# LED_Driver_-_2.net
KiCad netlist of a schematic drawn in Altium Designer
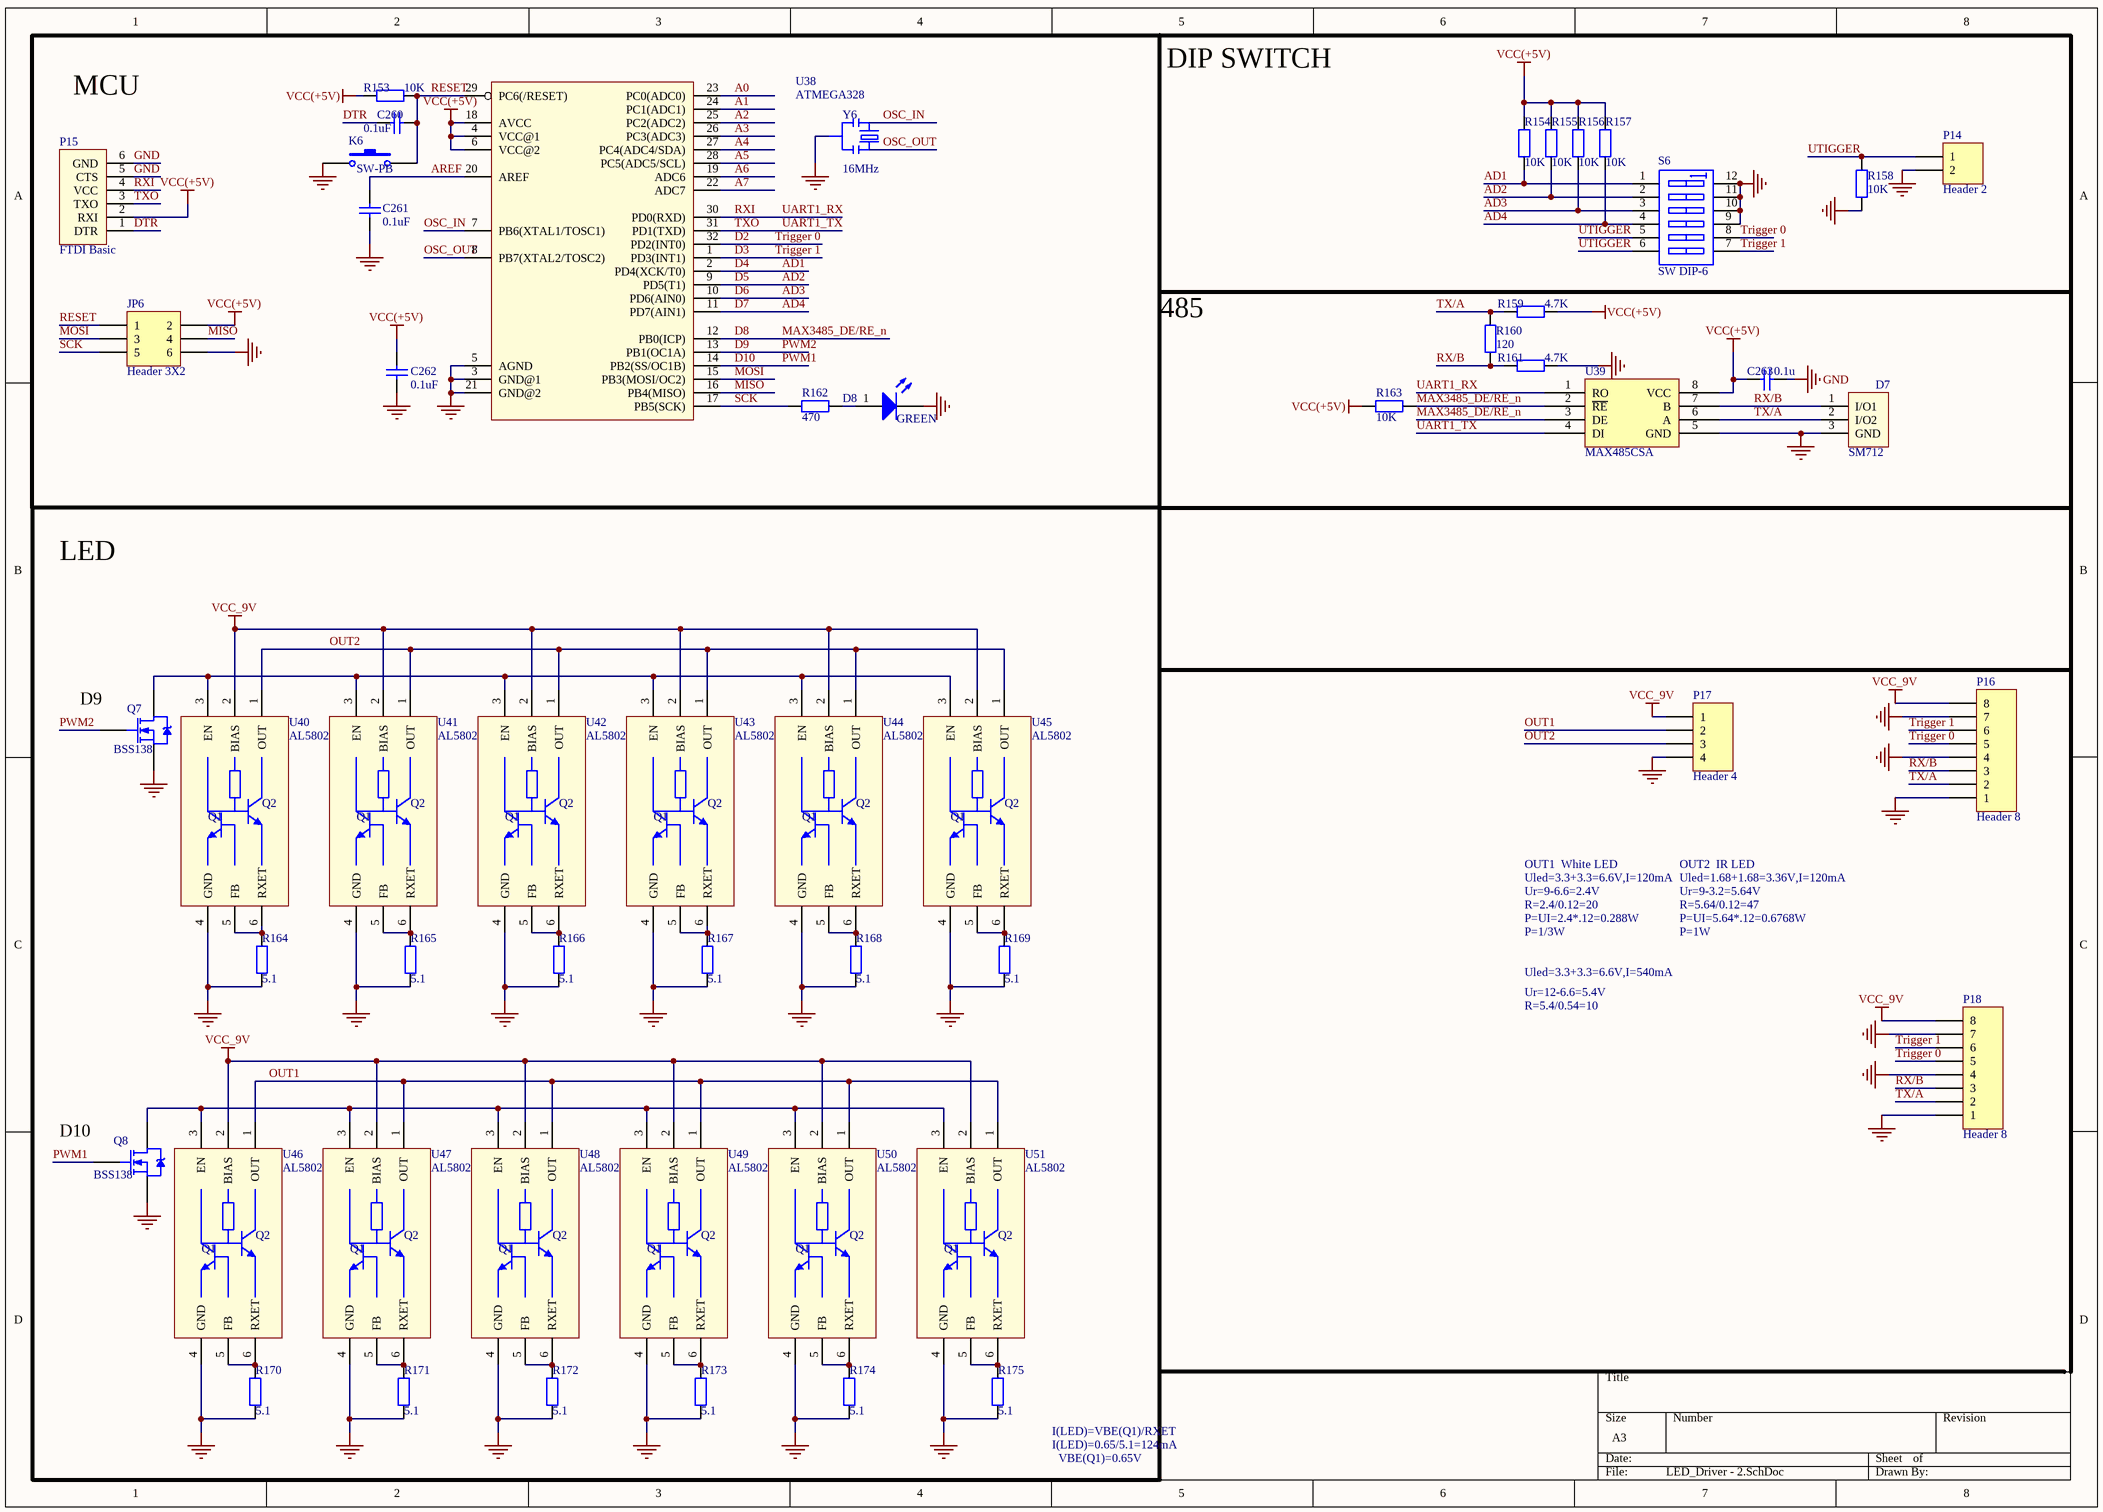
[diagram p0: LED_Driver - 2.SchDoc]

(export (version "E")
  (design (tool "Eeschema 10.0.6"))
  (components
    (comp (ref "C260")
      (value "0.1uF")
      (footprint "C0603")
      (description "Capacitor")
      (fields (field (name "IPARTNUMBER") "C100nF25V10%X7R") (field (name "VOLTAGE") "25V"))
      (libsource (lib "Schlib1") (part "CAP SMT C100nF25V10%X7R"))
    )
    (comp (ref "C261")
      (value "0.1uF")
      (footprint "C0603")
      (description "Capacitor")
      (fields (field (name "IPARTNUMBER") "C100nF25V10%X7R") (field (name "VOLTAGE") "25V"))
      (libsource (lib "Schlib1") (part "CAP SMT C100nF25V10%X7R"))
    )
    (comp (ref "C262")
      (value "0.1uF")
      (footprint "C0603")
      (description "Capacitor")
      (fields (field (name "IPARTNUMBER") "C100nF25V10%X7R") (field (name "VOLTAGE") "25V"))
      (libsource (lib "Schlib1") (part "CAP SMT C100nF25V10%X7R"))
    )
    (comp (ref "C263")
      (value "0.1u")
      (footprint "C0603")
      (description "Capacitor")
      (fields (field (name "PUBLISHER") "Altium Limited"))
      (libsource (lib "Miscellaneous Devices") (part "Cap"))
    )
    (comp (ref "D7")
      (value "SM712")
      (footprint "SOT23-3")
      (libsource (lib "STM32F4_CAM V2.0") (part "SM712"))
    )
    (comp (ref "D8")
      (value "GREEN")
      (footprint "LED0805")
      (description "Typical INFRARED GaAs LED")
      (fields (field (name "PUBLISHER") "Altium Limited"))
      (libsource (lib "DM642") (part "LED0"))
    )
    (comp (ref "JP6")
      (value "Header 3X2")
      (footprint "MHDR1X6")
      (description "Header, 3-Pin, Dual row")
      (fields (field (name "PUBLISHER") "Altium Limited"))
      (libsource (lib "Miscellaneous Connectors") (part "Header 3X2"))
    )
    (comp (ref "K6")
      (value "SW-PB")
      (footprint "157SW")
      (description "Switch")
      (fields (field (name "PUBLISHER") "Altium Limited"))
      (libsource (lib "Miscellaneous Devices") (part "SW-PB"))
    )
    (comp (ref "P14")
      (value "Header 2")
      (footprint "HDR1X2")
      (description "Header, 2-Pin")
      (fields (field (name "PUBLISHER") "Altium Limited"))
      (libsource (lib "Miscellaneous Connectors") (part "Header 2"))
    )
    (comp (ref "P15")
      (value "FTDI Basic")
      (footprint "MHDR1X6")
      (libsource (lib "PCB_Project1") (part "ARDUINO_SERIAL_PROGRAMPTH"))
    )
    (comp (ref "P16")
      (value "Header 8")
      (footprint "SH_1.25MM*8")
      (description "Header, 8-Pin")
      (fields (field (name "PUBLISHER") "Altium Limited"))
      (libsource (lib "Miscellaneous Connectors") (part "Header 8"))
    )
    (comp (ref "P17")
      (value "Header 4")
      (footprint "SMT_1.25MM*4")
      (description "Header, 4-Pin")
      (fields (field (name "PUBLISHER") "Altium Limited"))
      (libsource (lib "Miscellaneous Connectors") (part "Header 4"))
    )
    (comp (ref "P18")
      (value "Header 8")
      (footprint "SH_1.25MM*8")
      (description "Header, 8-Pin")
      (fields (field (name "PUBLISHER") "Altium Limited"))
      (libsource (lib "Miscellaneous Connectors") (part "Header 8"))
    )
    (comp (ref "Q7")
      (value "BSS138")
      (footprint "SOT-23 (Standard)")
      (fields
        (field (name "MANUFACTURER") "Fairchild Semiconductor")
        (field (name "MANUFACTURER PART NUMBER") "BSS123")
      )
      (libsource (lib "Miscellaneous_Devices") (part "NMOS"))
    )
    (comp (ref "Q8")
      (value "BSS138")
      (footprint "SOT-23 (Standard)")
      (fields
        (field (name "MANUFACTURER") "Fairchild Semiconductor")
        (field (name "MANUFACTURER PART NUMBER") "BSS123")
      )
      (libsource (lib "Miscellaneous_Devices") (part "NMOS"))
    )
    (comp (ref "R153")
      (value "10K")
      (footprint "R0603")
      (description "Resistor")
      (libsource (lib "") (part "Res2_2"))
    )
    (comp (ref "R154")
      (value "10K")
      (footprint "R0603")
      (description "Resistor")
      (libsource (lib "DM642") (part "Res2"))
    )
    (comp (ref "R155")
      (value "10K")
      (footprint "R0603")
      (description "Resistor")
      (libsource (lib "DM642") (part "Res2"))
    )
    (comp (ref "R156")
      (value "10K")
      (footprint "R0603")
      (description "Resistor")
      (libsource (lib "DM642") (part "Res2"))
    )
    (comp (ref "R157")
      (value "10K")
      (footprint "R0603")
      (description "Resistor")
      (libsource (lib "DM642") (part "Res2"))
    )
    (comp (ref "R158")
      (value "10K")
      (footprint "R0603")
      (description "Resistor")
      (fields (field (name "PUBLISHER") "Altium Limited"))
      (libsource (lib "Miscellaneous Devices") (part "Res2"))
    )
    (comp (ref "R159")
      (value "4.7K")
      (footprint "R0603")
      (description "Resistor")
      (libsource (lib "") (part "Res2_1"))
    )
    (comp (ref "R160")
      (value "120")
      (footprint "R0603")
      (description "Resistor")
      (libsource (lib "DM642") (part "Res2"))
    )
    (comp (ref "R161")
      (value "4.7K")
      (footprint "R0603")
      (description "Resistor")
      (libsource (lib "") (part "Res2_1"))
    )
    (comp (ref "R162")
      (value "470")
      (footprint "R0603")
      (description "Resistor")
      (libsource (lib "") (part "Res2_2"))
    )
    (comp (ref "R163")
      (value "10K")
      (footprint "R0603")
      (description "Resistor")
      (libsource (lib "") (part "Res2_1"))
    )
    (comp (ref "R164")
      (value "5.1")
      (footprint "R0603")
      (description "Resistor")
      (libsource (lib "DM642") (part "Res2"))
    )
    (comp (ref "R165")
      (value "5.1")
      (footprint "R0603")
      (description "Resistor")
      (libsource (lib "DM642") (part "Res2"))
    )
    (comp (ref "R166")
      (value "5.1")
      (footprint "R0603")
      (description "Resistor")
      (libsource (lib "DM642") (part "Res2"))
    )
    (comp (ref "R167")
      (value "5.1")
      (footprint "R0603")
      (description "Resistor")
      (libsource (lib "DM642") (part "Res2"))
    )
    (comp (ref "R168")
      (value "5.1")
      (footprint "R0603")
      (description "Resistor")
      (libsource (lib "DM642") (part "Res2"))
    )
    (comp (ref "R169")
      (value "5.1")
      (footprint "R0603")
      (description "Resistor")
      (libsource (lib "DM642") (part "Res2"))
    )
    (comp (ref "R170")
      (value "5.1")
      (footprint "R0603")
      (description "Resistor")
      (libsource (lib "DM642") (part "Res2"))
    )
    (comp (ref "R171")
      (value "5.1")
      (footprint "R0603")
      (description "Resistor")
      (libsource (lib "DM642") (part "Res2"))
    )
    (comp (ref "R172")
      (value "5.1")
      (footprint "R0603")
      (description "Resistor")
      (libsource (lib "DM642") (part "Res2"))
    )
    (comp (ref "R173")
      (value "5.1")
      (footprint "R0603")
      (description "Resistor")
      (libsource (lib "DM642") (part "Res2"))
    )
    (comp (ref "R174")
      (value "5.1")
      (footprint "R0603")
      (description "Resistor")
      (libsource (lib "DM642") (part "Res2"))
    )
    (comp (ref "R175")
      (value "5.1")
      (footprint "R0603")
      (description "Resistor")
      (libsource (lib "DM642") (part "Res2"))
    )
    (comp (ref "S6")
      (value "SW DIP-6")
      (footprint "DIP_SW_6WAY_SMD")
      (description "DIP Switch, 6 Position, SPST")
      (fields (field (name "PUBLISHER") "Altium Limited"))
      (libsource (lib "Miscellaneous Devices") (part "SW DIP-6"))
    )
    (comp (ref "U38")
      (value "ATMEGA328")
      (footprint "TQFP32-08")
      (libsource (lib "PCB_Project1") (part "ATMEGA168"))
    )
    (comp (ref "U39")
      (value "MAX485CSA")
      (footprint "SOIC-8")
      (libsource (lib "STM32F4_CAM V1.2") (part "MAX3485CSA"))
    )
    (comp (ref "U40") (value "AL5802") (footprint "SOT26") (libsource (lib "LED") (part "AL5802")))
    (comp (ref "U41") (value "AL5802") (footprint "SOT26") (libsource (lib "LED") (part "AL5802")))
    (comp (ref "U42") (value "AL5802") (footprint "SOT26") (libsource (lib "LED") (part "AL5802")))
    (comp (ref "U43") (value "AL5802") (footprint "SOT26") (libsource (lib "LED") (part "AL5802")))
    (comp (ref "U44") (value "AL5802") (footprint "SOT26") (libsource (lib "LED") (part "AL5802")))
    (comp (ref "U45") (value "AL5802") (footprint "SOT26") (libsource (lib "LED") (part "AL5802")))
    (comp (ref "U46") (value "AL5802") (footprint "SOT26") (libsource (lib "LED") (part "AL5802")))
    (comp (ref "U47") (value "AL5802") (footprint "SOT26") (libsource (lib "LED") (part "AL5802")))
    (comp (ref "U48") (value "AL5802") (footprint "SOT26") (libsource (lib "LED") (part "AL5802")))
    (comp (ref "U49") (value "AL5802") (footprint "SOT26") (libsource (lib "LED") (part "AL5802")))
    (comp (ref "U50") (value "AL5802") (footprint "SOT26") (libsource (lib "LED") (part "AL5802")))
    (comp (ref "U51") (value "AL5802") (footprint "SOT26") (libsource (lib "LED") (part "AL5802")))
    (comp (ref "Y6")
      (value "16MHz")
      (footprint "RESONATOR-SMD")
      (libsource (lib "SparkFun") (part "RESONATORSMD"))
    )
  )
  (nets
    (net (code "1") (name "/A0") (class "Default")
      (node (ref "U38") (pin "23") (pinfunction "PC0(ADC0)_23") (pintype "passive"))
    )
    (net (code "2") (name "/A1") (class "Default")
      (node (ref "U38") (pin "24") (pinfunction "PC1(ADC1)_24") (pintype "passive"))
    )
    (net (code "3") (name "/A2") (class "Default")
      (node (ref "U38") (pin "25") (pinfunction "PC2(ADC2)_25") (pintype "passive"))
    )
    (net (code "4") (name "/A3") (class "Default")
      (node (ref "U38") (pin "26") (pinfunction "PC3(ADC3)_26") (pintype "passive"))
    )
    (net (code "5") (name "/A4") (class "Default")
      (node (ref "U38") (pin "27") (pinfunction "PC4(ADC4/SDA)_27") (pintype "passive"))
    )
    (net (code "6") (name "/A5") (class "Default")
      (node (ref "U38") (pin "28") (pinfunction "PC5(ADC5/SCL)_28") (pintype "passive"))
    )
    (net (code "7") (name "/A6") (class "Default")
      (node (ref "U38") (pin "19") (pinfunction "ADC6_19") (pintype "passive"))
    )
    (net (code "8") (name "/A7") (class "Default")
      (node (ref "U38") (pin "22") (pinfunction "ADC7_22") (pintype "passive"))
    )
    (net (code "9") (name "/AD1") (class "Default")
      (node (ref "R154") (pin "2") (pinfunction "2_2") (pintype "passive"))
      (node (ref "S6") (pin "1") (pinfunction "A1_1") (pintype "passive"))
      (node (ref "U38") (pin "2") (pinfunction "PD4(XCK/T0)_2") (pintype "passive"))
    )
    (net (code "10") (name "/AD2") (class "Default")
      (node (ref "R155") (pin "2") (pinfunction "2_2") (pintype "passive"))
      (node (ref "S6") (pin "2") (pinfunction "A2_2") (pintype "passive"))
      (node (ref "U38") (pin "9") (pinfunction "PD5(T1)_9") (pintype "passive"))
    )
    (net (code "11") (name "/AD3") (class "Default")
      (node (ref "R156") (pin "2") (pinfunction "2_2") (pintype "passive"))
      (node (ref "S6") (pin "3") (pinfunction "A3_3") (pintype "passive"))
      (node (ref "U38") (pin "10") (pinfunction "PD6(AIN0)_10") (pintype "passive"))
    )
    (net (code "12") (name "/AD4") (class "Default")
      (node (ref "R157") (pin "2") (pinfunction "2_2") (pintype "passive"))
      (node (ref "S6") (pin "4") (pinfunction "A4_4") (pintype "passive"))
      (node (ref "U38") (pin "11") (pinfunction "PD7(AIN1)_11") (pintype "passive"))
    )
    (net (code "13") (name "/AREF") (class "Default")
      (node (ref "C261") (pin "2") (pinfunction "2_2") (pintype "passive"))
      (node (ref "U38") (pin "20") (pinfunction "AREF_20") (pintype "passive"))
    )
    (net (code "14") (name "/D2") (class "Default")
      (node (ref "P16") (pin "5") (pinfunction "5_5") (pintype "passive"))
      (node (ref "P18") (pin "5") (pinfunction "5_5") (pintype "passive"))
      (node (ref "S6") (pin "8") (pinfunction "B5_8") (pintype "passive"))
      (node (ref "U38") (pin "32") (pinfunction "PD2(INT0)_32") (pintype "passive"))
    )
    (net (code "15") (name "/D3") (class "Default")
      (node (ref "P16") (pin "6") (pinfunction "6_6") (pintype "passive"))
      (node (ref "P18") (pin "6") (pinfunction "6_6") (pintype "passive"))
      (node (ref "S6") (pin "7") (pinfunction "B6_7") (pintype "passive"))
      (node (ref "U38") (pin "1") (pinfunction "PD3(INT1)_1") (pintype "passive"))
    )
    (net (code "16") (name "/D8") (class "Default")
      (node (ref "R163") (pin "1") (pinfunction "1_1") (pintype "passive"))
      (node (ref "U38") (pin "12") (pinfunction "PB0(ICP)_12") (pintype "passive"))
      (node (ref "U39") (pin "2") (pinfunction "~{RE}_2") (pintype "passive"))
      (node (ref "U39") (pin "3") (pinfunction "DE_3") (pintype "passive"))
    )
    (net (code "17") (name "/D9") (class "Default")
      (node (ref "Q7") (pin "G") (pinfunction "G_G") (pintype "passive"))
      (node (ref "U38") (pin "13") (pinfunction "PB1(OC1A)_13") (pintype "passive"))
    )
    (net (code "18") (name "/D10") (class "Default")
      (node (ref "Q8") (pin "G") (pinfunction "G_G") (pintype "passive"))
      (node (ref "U38") (pin "14") (pinfunction "PB2(SS/OC1B)_14") (pintype "passive"))
    )
    (net (code "19") (name "/DTR") (class "Default")
      (node (ref "C260") (pin "1") (pinfunction "1_1") (pintype "passive"))
      (node (ref "P15") (pin "1") (pinfunction "DTR_1") (pintype "passive"))
    )
    (net (code "20") (name "/MISO") (class "Default")
      (node (ref "JP6") (pin "4") (pinfunction "4_4") (pintype "passive"))
      (node (ref "U38") (pin "16") (pinfunction "PB4(MISO)_16") (pintype "passive"))
    )
    (net (code "21") (name "/MOSI") (class "Default")
      (node (ref "JP6") (pin "3") (pinfunction "3_3") (pintype "passive"))
      (node (ref "U38") (pin "15") (pinfunction "PB3(MOSI/OC2)_15") (pintype "passive"))
    )
    (net (code "22") (name "/OSC_IN") (class "Default")
      (node (ref "U38") (pin "7") (pinfunction "PB6(XTAL1/TOSC1)_7") (pintype "passive"))
      (node (ref "Y6") (pin "3") (pinfunction "3_3") (pintype "passive"))
    )
    (net (code "23") (name "/OSC_OUT") (class "Default")
      (node (ref "U38") (pin "8") (pinfunction "PB7(XTAL2/TOSC2)_8") (pintype "passive"))
      (node (ref "Y6") (pin "1") (pinfunction "1_1") (pintype "passive"))
    )
    (net (code "24") (name "/OUT1") (class "Default")
      (node (ref "P17") (pin "2") (pinfunction "2_2") (pintype "passive"))
      (node (ref "U46") (pin "1") (pinfunction "OUT_1") (pintype "passive"))
      (node (ref "U47") (pin "1") (pinfunction "OUT_1") (pintype "passive"))
      (node (ref "U48") (pin "1") (pinfunction "OUT_1") (pintype "passive"))
      (node (ref "U49") (pin "1") (pinfunction "OUT_1") (pintype "passive"))
      (node (ref "U50") (pin "1") (pinfunction "OUT_1") (pintype "passive"))
      (node (ref "U51") (pin "1") (pinfunction "OUT_1") (pintype "passive"))
    )
    (net (code "25") (name "/OUT2") (class "Default")
      (node (ref "P17") (pin "3") (pinfunction "3_3") (pintype "passive"))
      (node (ref "U40") (pin "1") (pinfunction "OUT_1") (pintype "passive"))
      (node (ref "U41") (pin "1") (pinfunction "OUT_1") (pintype "passive"))
      (node (ref "U42") (pin "1") (pinfunction "OUT_1") (pintype "passive"))
      (node (ref "U43") (pin "1") (pinfunction "OUT_1") (pintype "passive"))
      (node (ref "U44") (pin "1") (pinfunction "OUT_1") (pintype "passive"))
      (node (ref "U45") (pin "1") (pinfunction "OUT_1") (pintype "passive"))
    )
    (net (code "26") (name "/RESET") (class "Default")
      (node (ref "C260") (pin "2") (pinfunction "2_2") (pintype "passive"))
      (node (ref "JP6") (pin "1") (pinfunction "1_1") (pintype "passive"))
      (node (ref "K6") (pin "2") (pinfunction "2_2") (pintype "passive"))
      (node (ref "R153") (pin "2") (pinfunction "2_2") (pintype "passive"))
      (node (ref "U38") (pin "29") (pinfunction "PC6(/RESET)_29") (pintype "passive"))
    )
    (net (code "27") (name "/RXI") (class "Default")
      (node (ref "P15") (pin "4") (pinfunction "VCC_4") (pintype "passive"))
      (node (ref "U38") (pin "30") (pinfunction "PD0(RXD)_30") (pintype "passive"))
      (node (ref "U39") (pin "1") (pinfunction "RO_1") (pintype "passive"))
    )
    (net (code "28") (name "/RX{slash}B") (class "Default")
      (node (ref "D7") (pin "1") (pinfunction "I/O1_1") (pintype "passive"))
      (node (ref "P16") (pin "3") (pinfunction "3_3") (pintype "passive"))
      (node (ref "P18") (pin "3") (pinfunction "3_3") (pintype "passive"))
      (node (ref "R160") (pin "2") (pinfunction "2_2") (pintype "passive"))
      (node (ref "R161") (pin "2") (pinfunction "2_2") (pintype "passive"))
      (node (ref "U39") (pin "7") (pinfunction "B_7") (pintype "passive"))
    )
    (net (code "29") (name "/SCK") (class "Default")
      (node (ref "JP6") (pin "5") (pinfunction "5_5") (pintype "passive"))
      (node (ref "R162") (pin "1") (pinfunction "1_1") (pintype "passive"))
      (node (ref "U38") (pin "17") (pinfunction "PB5(SCK)_17") (pintype "passive"))
    )
    (net (code "30") (name "/TXO") (class "Default")
      (node (ref "P15") (pin "3") (pinfunction "TXO_3") (pintype "passive"))
      (node (ref "U38") (pin "31") (pinfunction "PD1(TXD)_31") (pintype "passive"))
      (node (ref "U39") (pin "4") (pinfunction "DI_4") (pintype "passive"))
    )
    (net (code "31") (name "/TX{slash}A") (class "Default")
      (node (ref "D7") (pin "2") (pinfunction "I/O2_2") (pintype "passive"))
      (node (ref "P16") (pin "2") (pinfunction "2_2") (pintype "passive"))
      (node (ref "P18") (pin "2") (pinfunction "2_2") (pintype "passive"))
      (node (ref "R159") (pin "2") (pinfunction "2_2") (pintype "passive"))
      (node (ref "R160") (pin "1") (pinfunction "1_1") (pintype "passive"))
      (node (ref "U39") (pin "6") (pinfunction "A_6") (pintype "passive"))
    )
    (net (code "32") (name "/UTIGGER") (class "Default")
      (node (ref "P14") (pin "1") (pinfunction "1_1") (pintype "passive"))
      (node (ref "R158") (pin "2") (pinfunction "2_2") (pintype "passive"))
      (node (ref "S6") (pin "5") (pinfunction "A5_5") (pintype "passive"))
      (node (ref "S6") (pin "6") (pinfunction "A6_6") (pintype "passive"))
    )
    (net (code "33") (name "GND") (class "Default")
      (node (ref "C261") (pin "1") (pinfunction "1_1") (pintype "passive"))
      (node (ref "C262") (pin "2") (pinfunction "2_2") (pintype "passive"))
      (node (ref "C263") (pin "1") (pinfunction "1_1") (pintype "passive"))
      (node (ref "D7") (pin "3") (pinfunction "GND_3") (pintype "passive"))
      (node (ref "D8") (pin "2") (pinfunction "K_2") (pintype "passive"))
      (node (ref "JP6") (pin "6") (pinfunction "6_6") (pintype "passive"))
      (node (ref "K6") (pin "1") (pinfunction "1_1") (pintype "passive"))
      (node (ref "P14") (pin "2") (pinfunction "2_2") (pintype "passive"))
      (node (ref "P15") (pin "5") (pinfunction "CTS_5") (pintype "passive"))
      (node (ref "P15") (pin "6") (pinfunction "GND_6") (pintype "passive"))
      (node (ref "P16") (pin "1") (pinfunction "1_1") (pintype "passive"))
      (node (ref "P16") (pin "4") (pinfunction "4_4") (pintype "passive"))
      (node (ref "P16") (pin "7") (pinfunction "7_7") (pintype "passive"))
      (node (ref "P17") (pin "4") (pinfunction "4_4") (pintype "passive"))
      (node (ref "P18") (pin "1") (pinfunction "1_1") (pintype "passive"))
      (node (ref "P18") (pin "4") (pinfunction "4_4") (pintype "passive"))
      (node (ref "P18") (pin "7") (pinfunction "7_7") (pintype "passive"))
      (node (ref "Q7") (pin "S") (pinfunction "S_S") (pintype "passive"))
      (node (ref "Q8") (pin "S") (pinfunction "S_S") (pintype "passive"))
      (node (ref "R158") (pin "1") (pinfunction "1_1") (pintype "passive"))
      (node (ref "R161") (pin "1") (pinfunction "1_1") (pintype "passive"))
      (node (ref "R164") (pin "2") (pinfunction "2_2") (pintype "passive"))
      (node (ref "R165") (pin "2") (pinfunction "2_2") (pintype "passive"))
      (node (ref "R166") (pin "2") (pinfunction "2_2") (pintype "passive"))
      (node (ref "R167") (pin "2") (pinfunction "2_2") (pintype "passive"))
      (node (ref "R168") (pin "2") (pinfunction "2_2") (pintype "passive"))
      (node (ref "R169") (pin "2") (pinfunction "2_2") (pintype "passive"))
      (node (ref "R170") (pin "2") (pinfunction "2_2") (pintype "passive"))
      (node (ref "R171") (pin "2") (pinfunction "2_2") (pintype "passive"))
      (node (ref "R172") (pin "2") (pinfunction "2_2") (pintype "passive"))
      (node (ref "R173") (pin "2") (pinfunction "2_2") (pintype "passive"))
      (node (ref "R174") (pin "2") (pinfunction "2_2") (pintype "passive"))
      (node (ref "R175") (pin "2") (pinfunction "2_2") (pintype "passive"))
      (node (ref "S6") (pin "10") (pinfunction "B3_10") (pintype "passive"))
      (node (ref "S6") (pin "11") (pinfunction "B2_11") (pintype "passive"))
      (node (ref "S6") (pin "12") (pinfunction "B1_12") (pintype "passive"))
      (node (ref "S6") (pin "9") (pinfunction "B4_9") (pintype "passive"))
      (node (ref "U38") (pin "21") (pinfunction "GND@2_21") (pintype "passive"))
      (node (ref "U38") (pin "3") (pinfunction "GND@1_3") (pintype "passive"))
      (node (ref "U38") (pin "5") (pinfunction "AGND_5") (pintype "passive"))
      (node (ref "U39") (pin "5") (pinfunction "GND_5") (pintype "passive"))
      (node (ref "U40") (pin "4") (pinfunction "GND_4") (pintype "passive"))
      (node (ref "U41") (pin "4") (pinfunction "GND_4") (pintype "passive"))
      (node (ref "U42") (pin "4") (pinfunction "GND_4") (pintype "passive"))
      (node (ref "U43") (pin "4") (pinfunction "GND_4") (pintype "passive"))
      (node (ref "U44") (pin "4") (pinfunction "GND_4") (pintype "passive"))
      (node (ref "U45") (pin "4") (pinfunction "GND_4") (pintype "passive"))
      (node (ref "U46") (pin "4") (pinfunction "GND_4") (pintype "passive"))
      (node (ref "U47") (pin "4") (pinfunction "GND_4") (pintype "passive"))
      (node (ref "U48") (pin "4") (pinfunction "GND_4") (pintype "passive"))
      (node (ref "U49") (pin "4") (pinfunction "GND_4") (pintype "passive"))
      (node (ref "U50") (pin "4") (pinfunction "GND_4") (pintype "passive"))
      (node (ref "U51") (pin "4") (pinfunction "GND_4") (pintype "passive"))
      (node (ref "Y6") (pin "2") (pinfunction "2_2") (pintype "passive"))
    )
    (net (code "34") (name "Net-(D8-A)") (class "Default")
      (node (ref "D8") (pin "1") (pinfunction "A_1") (pintype "passive"))
      (node (ref "R162") (pin "2") (pinfunction "2_2") (pintype "passive"))
    )
    (net (code "35") (name "Net-(U40-EN)") (class "Default")
      (node (ref "Q7") (pin "D") (pinfunction "D_D") (pintype "passive"))
      (node (ref "U40") (pin "3") (pinfunction "EN_3") (pintype "passive"))
      (node (ref "U41") (pin "3") (pinfunction "EN_3") (pintype "passive"))
      (node (ref "U42") (pin "3") (pinfunction "EN_3") (pintype "passive"))
      (node (ref "U43") (pin "3") (pinfunction "EN_3") (pintype "passive"))
      (node (ref "U44") (pin "3") (pinfunction "EN_3") (pintype "passive"))
      (node (ref "U45") (pin "3") (pinfunction "EN_3") (pintype "passive"))
    )
    (net (code "36") (name "Net-(U40-FB)") (class "Default")
      (node (ref "R164") (pin "1") (pinfunction "1_1") (pintype "passive"))
      (node (ref "U40") (pin "5") (pinfunction "FB_5") (pintype "passive"))
      (node (ref "U40") (pin "6") (pinfunction "RXET_6") (pintype "passive"))
    )
    (net (code "37") (name "Net-(U41-FB)") (class "Default")
      (node (ref "R165") (pin "1") (pinfunction "1_1") (pintype "passive"))
      (node (ref "U41") (pin "5") (pinfunction "FB_5") (pintype "passive"))
      (node (ref "U41") (pin "6") (pinfunction "RXET_6") (pintype "passive"))
    )
    (net (code "38") (name "Net-(U42-FB)") (class "Default")
      (node (ref "R166") (pin "1") (pinfunction "1_1") (pintype "passive"))
      (node (ref "U42") (pin "5") (pinfunction "FB_5") (pintype "passive"))
      (node (ref "U42") (pin "6") (pinfunction "RXET_6") (pintype "passive"))
    )
    (net (code "39") (name "Net-(U43-FB)") (class "Default")
      (node (ref "R167") (pin "1") (pinfunction "1_1") (pintype "passive"))
      (node (ref "U43") (pin "5") (pinfunction "FB_5") (pintype "passive"))
      (node (ref "U43") (pin "6") (pinfunction "RXET_6") (pintype "passive"))
    )
    (net (code "40") (name "Net-(U44-FB)") (class "Default")
      (node (ref "R168") (pin "1") (pinfunction "1_1") (pintype "passive"))
      (node (ref "U44") (pin "5") (pinfunction "FB_5") (pintype "passive"))
      (node (ref "U44") (pin "6") (pinfunction "RXET_6") (pintype "passive"))
    )
    (net (code "41") (name "Net-(U45-FB)") (class "Default")
      (node (ref "R169") (pin "1") (pinfunction "1_1") (pintype "passive"))
      (node (ref "U45") (pin "5") (pinfunction "FB_5") (pintype "passive"))
      (node (ref "U45") (pin "6") (pinfunction "RXET_6") (pintype "passive"))
    )
    (net (code "42") (name "Net-(U46-EN)") (class "Default")
      (node (ref "Q8") (pin "D") (pinfunction "D_D") (pintype "passive"))
      (node (ref "U46") (pin "3") (pinfunction "EN_3") (pintype "passive"))
      (node (ref "U47") (pin "3") (pinfunction "EN_3") (pintype "passive"))
      (node (ref "U48") (pin "3") (pinfunction "EN_3") (pintype "passive"))
      (node (ref "U49") (pin "3") (pinfunction "EN_3") (pintype "passive"))
      (node (ref "U50") (pin "3") (pinfunction "EN_3") (pintype "passive"))
      (node (ref "U51") (pin "3") (pinfunction "EN_3") (pintype "passive"))
    )
    (net (code "43") (name "Net-(U46-FB)") (class "Default")
      (node (ref "R170") (pin "1") (pinfunction "1_1") (pintype "passive"))
      (node (ref "U46") (pin "5") (pinfunction "FB_5") (pintype "passive"))
      (node (ref "U46") (pin "6") (pinfunction "RXET_6") (pintype "passive"))
    )
    (net (code "44") (name "Net-(U47-FB)") (class "Default")
      (node (ref "R171") (pin "1") (pinfunction "1_1") (pintype "passive"))
      (node (ref "U47") (pin "5") (pinfunction "FB_5") (pintype "passive"))
      (node (ref "U47") (pin "6") (pinfunction "RXET_6") (pintype "passive"))
    )
    (net (code "45") (name "Net-(U48-FB)") (class "Default")
      (node (ref "R172") (pin "1") (pinfunction "1_1") (pintype "passive"))
      (node (ref "U48") (pin "5") (pinfunction "FB_5") (pintype "passive"))
      (node (ref "U48") (pin "6") (pinfunction "RXET_6") (pintype "passive"))
    )
    (net (code "46") (name "Net-(U49-FB)") (class "Default")
      (node (ref "R173") (pin "1") (pinfunction "1_1") (pintype "passive"))
      (node (ref "U49") (pin "5") (pinfunction "FB_5") (pintype "passive"))
      (node (ref "U49") (pin "6") (pinfunction "RXET_6") (pintype "passive"))
    )
    (net (code "47") (name "Net-(U50-FB)") (class "Default")
      (node (ref "R174") (pin "1") (pinfunction "1_1") (pintype "passive"))
      (node (ref "U50") (pin "5") (pinfunction "FB_5") (pintype "passive"))
      (node (ref "U50") (pin "6") (pinfunction "RXET_6") (pintype "passive"))
    )
    (net (code "48") (name "Net-(U51-FB)") (class "Default")
      (node (ref "R175") (pin "1") (pinfunction "1_1") (pintype "passive"))
      (node (ref "U51") (pin "5") (pinfunction "FB_5") (pintype "passive"))
      (node (ref "U51") (pin "6") (pinfunction "RXET_6") (pintype "passive"))
    )
    (net (code "49") (name "VCC(+5V)") (class "Default")
      (node (ref "C262") (pin "1") (pinfunction "1_1") (pintype "passive"))
      (node (ref "C263") (pin "2") (pinfunction "2_2") (pintype "passive"))
      (node (ref "JP6") (pin "2") (pinfunction "2_2") (pintype "passive"))
      (node (ref "P15") (pin "2") (pinfunction "RXI_2") (pintype "passive"))
      (node (ref "R153") (pin "1") (pinfunction "1_1") (pintype "passive"))
      (node (ref "R154") (pin "1") (pinfunction "1_1") (pintype "passive"))
      (node (ref "R155") (pin "1") (pinfunction "1_1") (pintype "passive"))
      (node (ref "R156") (pin "1") (pinfunction "1_1") (pintype "passive"))
      (node (ref "R157") (pin "1") (pinfunction "1_1") (pintype "passive"))
      (node (ref "R159") (pin "1") (pinfunction "1_1") (pintype "passive"))
      (node (ref "R163") (pin "2") (pinfunction "2_2") (pintype "passive"))
      (node (ref "U38") (pin "18") (pinfunction "AVCC_18") (pintype "passive"))
      (node (ref "U38") (pin "4") (pinfunction "VCC@1_4") (pintype "passive"))
      (node (ref "U38") (pin "6") (pinfunction "VCC@2_6") (pintype "passive"))
      (node (ref "U39") (pin "8") (pinfunction "VCC_8") (pintype "passive"))
    )
    (net (code "50") (name "VCC_9V") (class "Default")
      (node (ref "P16") (pin "8") (pinfunction "8_8") (pintype "passive"))
      (node (ref "P17") (pin "1") (pinfunction "1_1") (pintype "passive"))
      (node (ref "P18") (pin "8") (pinfunction "8_8") (pintype "passive"))
      (node (ref "U40") (pin "2") (pinfunction "BIAS_2") (pintype "passive"))
      (node (ref "U41") (pin "2") (pinfunction "BIAS_2") (pintype "passive"))
      (node (ref "U42") (pin "2") (pinfunction "BIAS_2") (pintype "passive"))
      (node (ref "U43") (pin "2") (pinfunction "BIAS_2") (pintype "passive"))
      (node (ref "U44") (pin "2") (pinfunction "BIAS_2") (pintype "passive"))
      (node (ref "U45") (pin "2") (pinfunction "BIAS_2") (pintype "passive"))
      (node (ref "U46") (pin "2") (pinfunction "BIAS_2") (pintype "passive"))
      (node (ref "U47") (pin "2") (pinfunction "BIAS_2") (pintype "passive"))
      (node (ref "U48") (pin "2") (pinfunction "BIAS_2") (pintype "passive"))
      (node (ref "U49") (pin "2") (pinfunction "BIAS_2") (pintype "passive"))
      (node (ref "U50") (pin "2") (pinfunction "BIAS_2") (pintype "passive"))
      (node (ref "U51") (pin "2") (pinfunction "BIAS_2") (pintype "passive"))
    )
  )
)
